# IO.net
KiCad netlist of a schematic drawn in Altium Designer
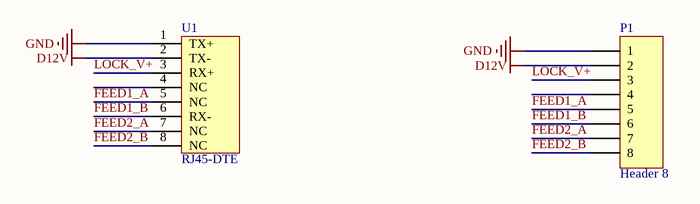
[diagram p0: IO.SchDoc]

(export (version "E")
  (design (tool "Eeschema 10.0.6"))
  (components
    (comp (ref "P1")
      (value "Header 8")
      (footprint "KF142R-5.08-8")
      (description "Header, 8-Pin")
      (fields (field (name "PUBLISHER") "Altium Limited"))
      (libsource (lib "lib_AD") (part "Header 8"))
    )
    (comp (ref "U1") (value "RJ45-DTE") (footprint "RJ45") (libsource (lib "lib_AD") (part "RJ45-DTE")))
  )
  (nets
    (net (code "1") (name "/FEED1_A") (class "Default")
      (node (ref "P1") (pin "5") (pinfunction "5_5") (pintype "passive"))
      (node (ref "U1") (pin "5") (pinfunction "NC_5") (pintype "passive"))
    )
    (net (code "2") (name "/FEED1_B") (class "Default")
      (node (ref "P1") (pin "6") (pinfunction "6_6") (pintype "passive"))
      (node (ref "U1") (pin "6") (pinfunction "RX-_6") (pintype "passive"))
    )
    (net (code "3") (name "/FEED2_A") (class "Default")
      (node (ref "P1") (pin "7") (pinfunction "7_7") (pintype "passive"))
      (node (ref "U1") (pin "7") (pinfunction "NC_7") (pintype "passive"))
    )
    (net (code "4") (name "/FEED2_B") (class "Default")
      (node (ref "P1") (pin "8") (pinfunction "8_8") (pintype "passive"))
      (node (ref "U1") (pin "8") (pinfunction "NC_8") (pintype "passive"))
    )
    (net (code "5") (name "/LOCK_V+") (class "Default")
      (node (ref "P1") (pin "3") (pinfunction "3_3") (pintype "passive"))
      (node (ref "U1") (pin "3") (pinfunction "RX+_3") (pintype "passive"))
    )
    (net (code "6") (name "D12V") (class "Default")
      (node (ref "P1") (pin "2") (pinfunction "2_2") (pintype "passive"))
      (node (ref "U1") (pin "2") (pinfunction "TX-_2") (pintype "passive"))
    )
    (net (code "7") (name "GND") (class "Default")
      (node (ref "P1") (pin "1") (pinfunction "1_1") (pintype "passive"))
      (node (ref "U1") (pin "1") (pinfunction "TX+_1") (pintype "passive"))
    )
    (net (code "8") (name "unconnected-(P1-Pad4)") (class "Default")
      (node (ref "P1") (pin "4") (pinfunction "4_4") (pintype "passive"))
    )
    (net (code "9") (name "unconnected-(U1-NC-Pad4)") (class "Default")
      (node (ref "U1") (pin "4") (pinfunction "NC_4") (pintype "passive"))
    )
  )
)
